# yakimenko_power_control.net
KiCad netlist of a schematic drawn in Altium Designer
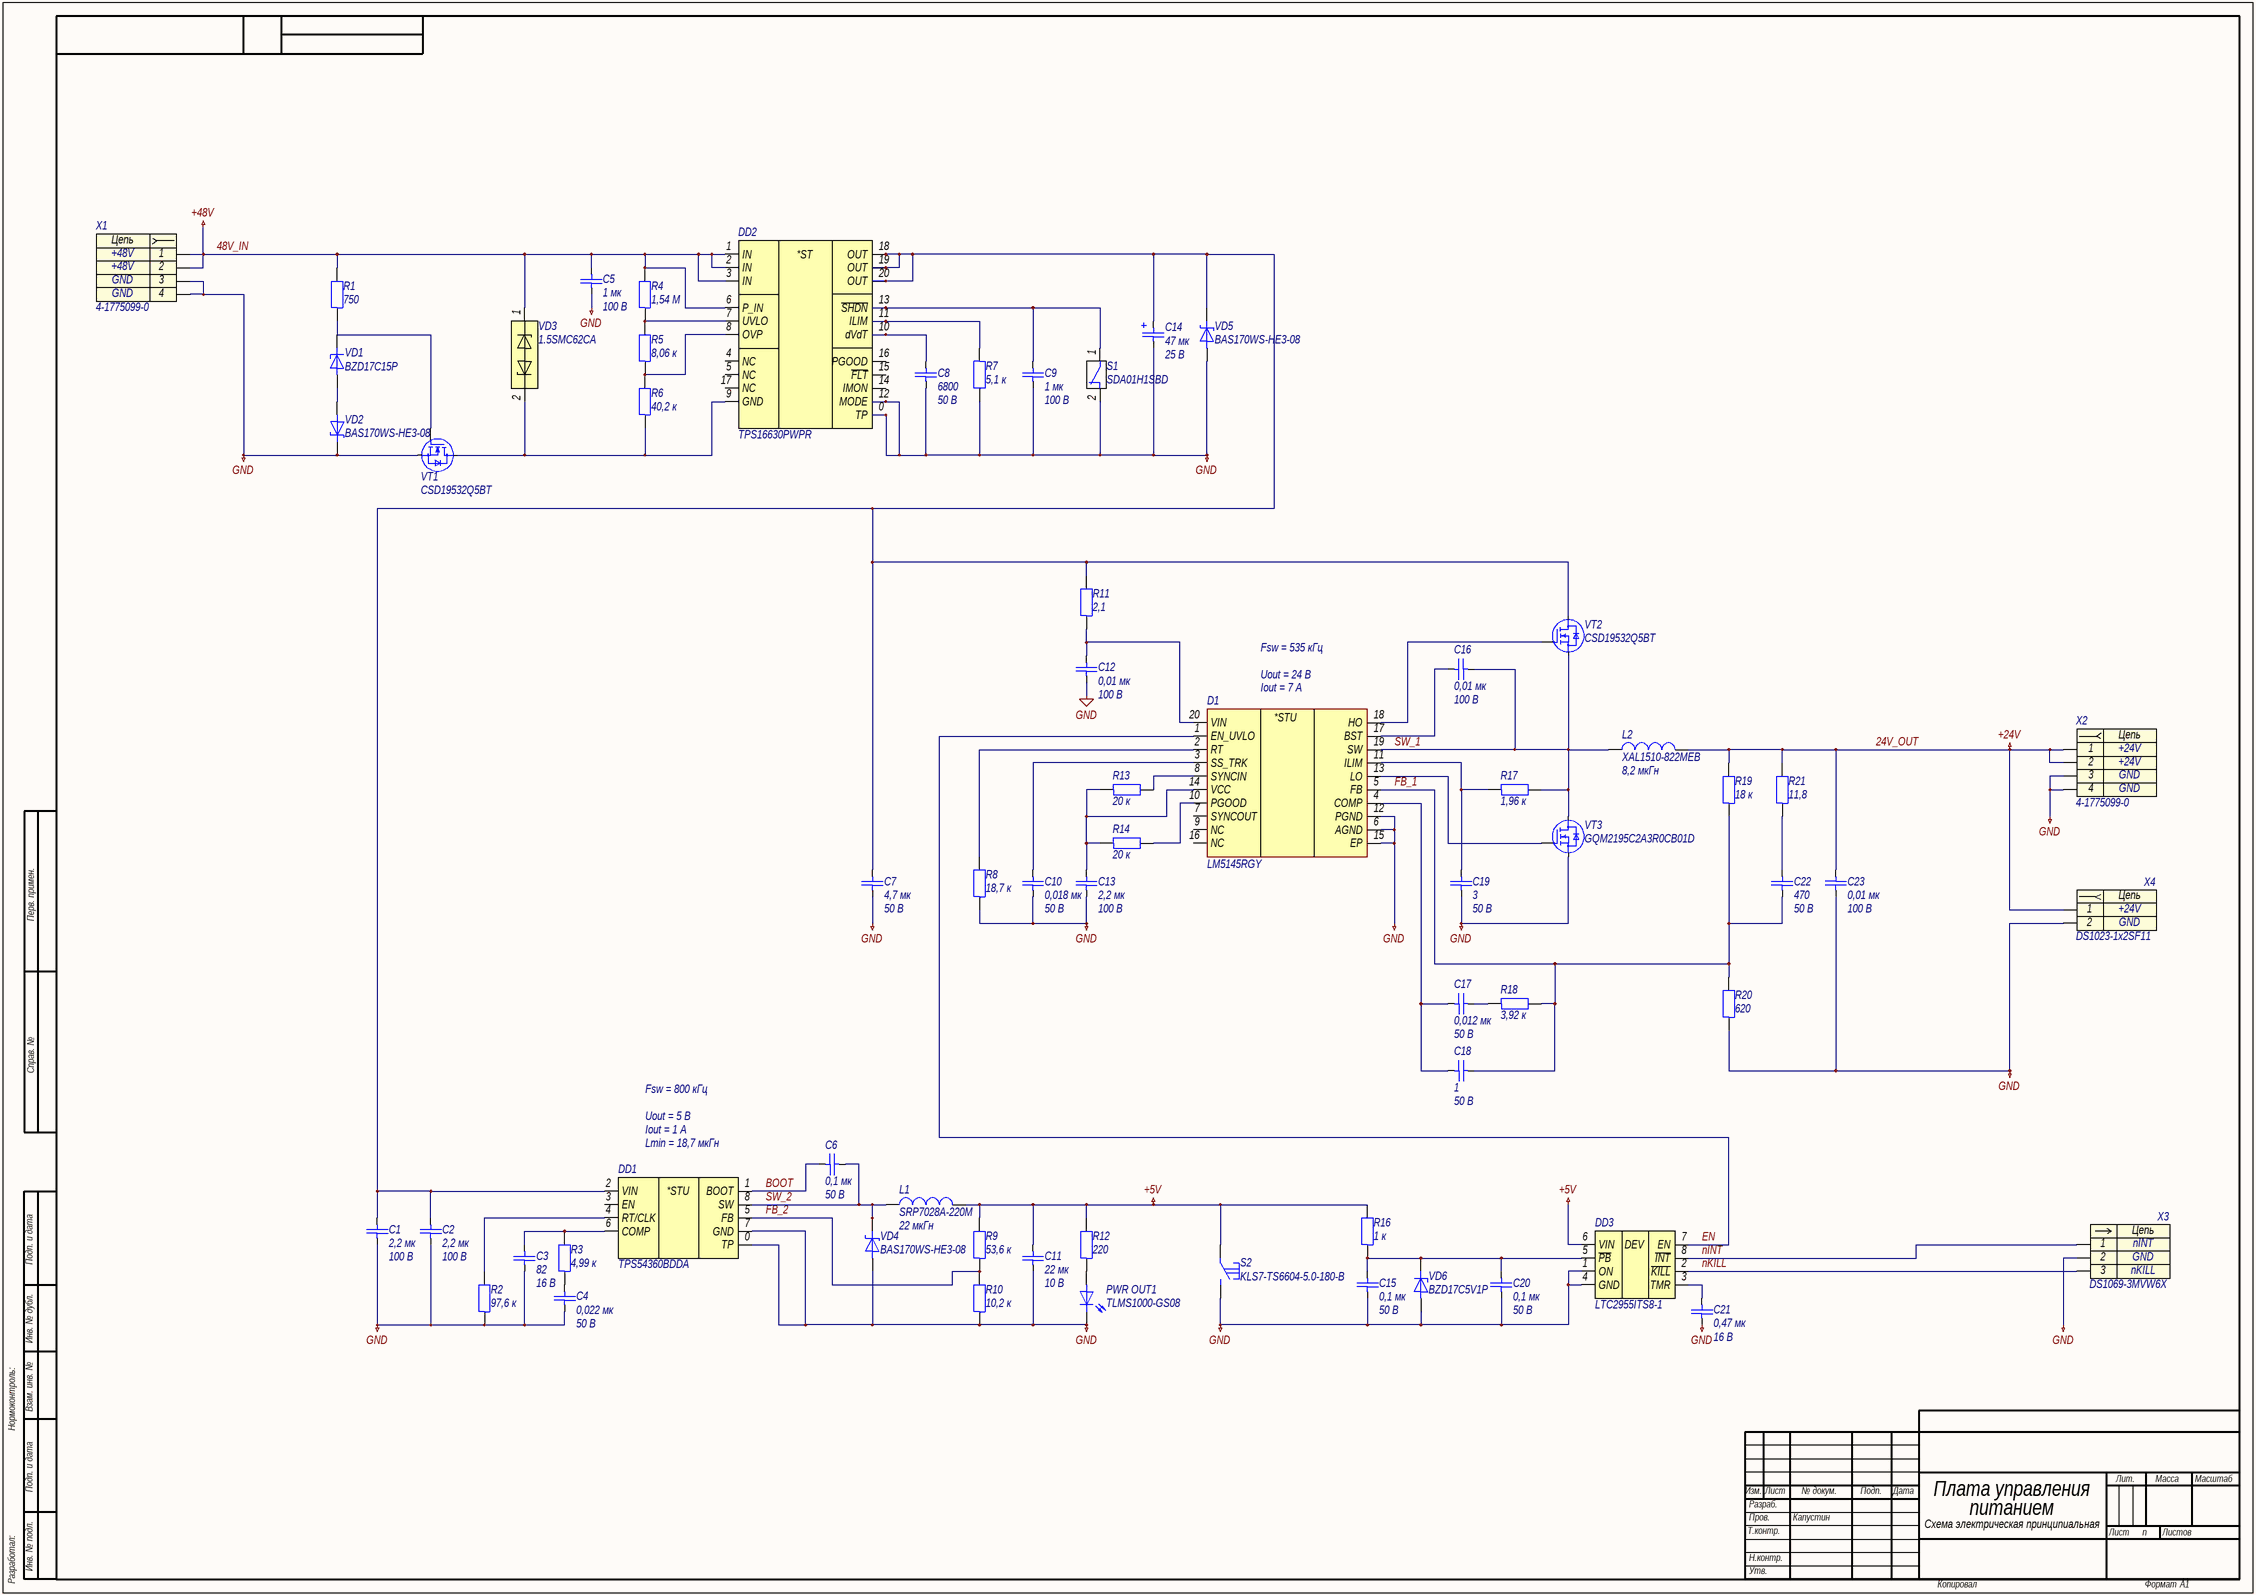
[diagram p0: yakimenko_power_control.SchDoc]

(export (version "E")
  (design (tool "Eeschema 10.0.6"))
  (components
    (comp (ref "C1")
      (value "2,2 мк")
      (footprint "C1206")
      (description "=Описание")
      (fields (field (name "НАПРЯЖЕНИЕ") "100 В"))
      (libsource (lib "Database_Students") (part "CAPACITOR-NONPOLAR"))
    )
    (comp (ref "C2")
      (value "2,2 мк")
      (footprint "C1206")
      (description "=Описание")
      (fields (field (name "НАПРЯЖЕНИЕ") "100 В"))
      (libsource (lib "Database_Students") (part "CAPACITOR-NONPOLAR"))
    )
    (comp (ref "C3")
      (value "82")
      (footprint "C0603")
      (description "=Описание")
      (fields (field (name "НАПРЯЖЕНИЕ") "16 В"))
      (libsource (lib "Database_Students") (part "CAPACITOR-NONPOLAR"))
    )
    (comp (ref "C4")
      (value "0,022 мк")
      (footprint "C0603")
      (description "=Описание")
      (fields (field (name "НАПРЯЖЕНИЕ") "50 В"))
      (libsource (lib "Database_Students") (part "CAPACITOR-NONPOLAR"))
    )
    (comp (ref "C5")
      (value "1 мк")
      (footprint "C1206")
      (description "=Описание")
      (fields (field (name "НАПРЯЖЕНИЕ") "100 В"))
      (libsource (lib "Database_Students") (part "CAPACITOR-NONPOLAR"))
    )
    (comp (ref "C6")
      (value "0,1 мк")
      (footprint "C0402")
      (description "=Описание")
      (fields (field (name "НАПРЯЖЕНИЕ") "50 В"))
      (libsource (lib "Database_Students") (part "CAPACITOR-NONPOLAR"))
    )
    (comp (ref "C7")
      (value "4,7 мк")
      (footprint "C0805")
      (description "=Описание")
      (fields (field (name "НАПРЯЖЕНИЕ") "50 В"))
      (libsource (lib "Database_Students") (part "CAPACITOR-NONPOLAR"))
    )
    (comp (ref "C8")
      (value "6800")
      (footprint "C0402")
      (description "=Описание")
      (fields (field (name "НАПРЯЖЕНИЕ") "50 В"))
      (libsource (lib "Database_Students") (part "CAPACITOR-NONPOLAR"))
    )
    (comp (ref "C9")
      (value "1 мк")
      (footprint "C1206")
      (description "=Описание")
      (fields (field (name "НАПРЯЖЕНИЕ") "100 В"))
      (libsource (lib "Database_Students") (part "CAPACITOR-NONPOLAR"))
    )
    (comp (ref "C10")
      (value "0,018 мк")
      (footprint "C0603")
      (description "=Описание")
      (fields (field (name "НАПРЯЖЕНИЕ") "50 В"))
      (libsource (lib "Database_Students") (part "CAPACITOR-NONPOLAR"))
    )
    (comp (ref "C11")
      (value "22 мк")
      (footprint "C0805")
      (description "=Описание")
      (fields (field (name "НАПРЯЖЕНИЕ") "10 В"))
      (libsource (lib "Database_Students") (part "CAPACITOR-NONPOLAR"))
    )
    (comp (ref "C12")
      (value "0,01 мк")
      (footprint "C0603")
      (description "=Описание")
      (fields (field (name "НАПРЯЖЕНИЕ") "100 В"))
      (libsource (lib "Database_Students") (part "CAPACITOR-NONPOLAR"))
    )
    (comp (ref "C13")
      (value "2,2 мк")
      (footprint "C1206")
      (description "=Описание")
      (fields (field (name "НАПРЯЖЕНИЕ") "100 В"))
      (libsource (lib "Database_Students") (part "CAPACITOR-NONPOLAR"))
    )
    (comp (ref "C14")
      (value "47 мк")
      (footprint "C7343-31")
      (description "=Описание")
      (fields (field (name "НАПРЯЖЕНИЕ") "25 В"))
      (libsource (lib "Database_Students") (part "CAPACITOR-POLAR"))
    )
    (comp (ref "C15")
      (value "0,1 мк")
      (footprint "C0402")
      (description "=Описание")
      (fields (field (name "НАПРЯЖЕНИЕ") "50 В"))
      (libsource (lib "Database_Students") (part "CAPACITOR-NONPOLAR"))
    )
    (comp (ref "C16")
      (value "0,01 мк")
      (footprint "C0603")
      (description "=Описание")
      (fields (field (name "НАПРЯЖЕНИЕ") "100 В"))
      (libsource (lib "Database_Students") (part "CAPACITOR-NONPOLAR"))
    )
    (comp (ref "C17")
      (value "0,012 мк")
      (footprint "C0603")
      (description "=Описание")
      (fields (field (name "НАПРЯЖЕНИЕ") "50 В"))
      (libsource (lib "Database_Students") (part "CAPACITOR-NONPOLAR"))
    )
    (comp (ref "C18")
      (value "1")
      (footprint "C0603")
      (description "=Описание")
      (fields (field (name "НАПРЯЖЕНИЕ") "50 В"))
      (libsource (lib "Database_Students") (part "CAPACITOR-NONPOLAR"))
    )
    (comp (ref "C19")
      (value "3")
      (footprint "C0603")
      (description "=Описание")
      (fields (field (name "НАПРЯЖЕНИЕ") "50 В"))
      (libsource (lib "Database_Students") (part "CAPACITOR-NONPOLAR"))
    )
    (comp (ref "C20")
      (value "0,1 мк")
      (footprint "C0402")
      (description "=Описание")
      (fields (field (name "НАПРЯЖЕНИЕ") "50 В"))
      (libsource (lib "Database_Students") (part "CAPACITOR-NONPOLAR"))
    )
    (comp (ref "C21")
      (value "0,47 мк")
      (footprint "C0603")
      (description "=Описание")
      (fields (field (name "НАПРЯЖЕНИЕ") "16 В"))
      (libsource (lib "Database_Students") (part "CAPACITOR-NONPOLAR"))
    )
    (comp (ref "C22")
      (value "470")
      (footprint "C0603")
      (description "=Описание")
      (fields (field (name "НАПРЯЖЕНИЕ") "50 В"))
      (libsource (lib "Database_Students") (part "CAPACITOR-NONPOLAR"))
    )
    (comp (ref "C23")
      (value "0,01 мк")
      (footprint "C0603")
      (description "=Описание")
      (fields (field (name "НАПРЯЖЕНИЕ") "100 В"))
      (libsource (lib "Database_Students") (part "CAPACITOR-NONPOLAR"))
    )
    (comp (ref "D1")
      (value "LM5145RGY")
      (footprint "VQFN-20-P50-450X350X100-L40X25-T270X170")
      (libsource (lib "yakimenko_power_control_lib") (part "LM5145RGY"))
    )
    (comp (ref "DD1")
      (value "TPS54360BDDA")
      (footprint "HSOIC-8-P127-490X390X170-L84X41-T310X240")
      (description "=Описание")
      (libsource (lib "Database_Students") (part "TPS54360BDDA"))
    )
    (comp (ref "DD2")
      (value "TPS16630PWPR")
      (footprint "HTSSOP-20-P65-650X440X120-L63X25-T296X296")
      (description "=Описание")
      (libsource (lib "Database_Students") (part "TPS16630PWPR"))
    )
    (comp (ref "DD3")
      (value "LTC2955ITS8-1")
      (footprint "SOT-23-8-P65-290X280X100")
      (description "=Описание")
      (libsource (lib "Database_Students") (part "LTC2955ITS8-1#TRMPBF"))
    )
    (comp (ref "L1")
      (value "SRP7028A-220M")
      (footprint "SRP-2-730X660X280")
      (description "=Описание")
      (fields (field (name "ИНДУКТИВНОСТЬ") "22 мкГн"))
      (libsource (lib "Database_Students") (part "INDUCTOR-COMMON"))
    )
    (comp (ref "L2")
      (value "XAL1510-822MEB")
      (footprint "XAL-2-1620X1520X1000")
      (description "=Описание")
      (fields (field (name "ИНДУКТИВНОСТЬ") "8,2 мкГн"))
      (libsource (lib "Database_Students") (part "INDUCTOR-COMMON"))
    )
    (comp (ref "PWR OUT1")
      (value "TLMS1000-GS08")
      (footprint "HL0603")
      (description "=Описание")
      (libsource (lib "Database_Students") (part "HL-COMMON"))
    )
    (comp (ref "R1")
      (value "750")
      (footprint "R0603")
      (description "=Описание")
      (libsource (lib "Database_Students") (part "R-COMMON"))
    )
    (comp (ref "R2")
      (value "97,6 к")
      (footprint "R0603")
      (description "=Описание")
      (libsource (lib "Database_Students") (part "R-COMMON"))
    )
    (comp (ref "R3")
      (value "4,99 к")
      (footprint "R0603")
      (description "=Описание")
      (libsource (lib "Database_Students") (part "R-COMMON"))
    )
    (comp (ref "R4")
      (value "1,54 М")
      (footprint "R0603")
      (description "=Описание")
      (libsource (lib "Database_Students") (part "R-COMMON"))
    )
    (comp (ref "R5")
      (value "8,06 к")
      (footprint "R0603")
      (description "=Описание")
      (libsource (lib "Database_Students") (part "R-COMMON"))
    )
    (comp (ref "R6")
      (value "40,2 к")
      (footprint "R0603")
      (description "=Описание")
      (libsource (lib "Database_Students") (part "R-COMMON"))
    )
    (comp (ref "R7")
      (value "5,1 к")
      (footprint "R0603")
      (description "=Описание")
      (libsource (lib "Database_Students") (part "R-COMMON"))
    )
    (comp (ref "R8")
      (value "18,7 к")
      (footprint "R0603")
      (description "=Описание")
      (libsource (lib "Database_Students") (part "RESISTOR-COMMON"))
    )
    (comp (ref "R9")
      (value "53,6 к")
      (footprint "R0603")
      (description "=Описание")
      (libsource (lib "Database_Students") (part "R-COMMON"))
    )
    (comp (ref "R10")
      (value "10,2 к")
      (footprint "R0603")
      (description "=Описание")
      (libsource (lib "Database_Students") (part "R-COMMON"))
    )
    (comp (ref "R11")
      (value "2,1")
      (footprint "R0603")
      (description "=Описание")
      (libsource (lib "Database_Students") (part "RESISTOR-COMMON"))
    )
    (comp (ref "R12")
      (value "220")
      (footprint "R0603")
      (description "=Описание")
      (libsource (lib "Database_Students") (part "R-COMMON"))
    )
    (comp (ref "R13")
      (value "20 к")
      (footprint "R0603")
      (description "=Описание")
      (libsource (lib "Database_Students") (part "RESISTOR-COMMON"))
    )
    (comp (ref "R14")
      (value "20 к")
      (footprint "R0603")
      (description "=Описание")
      (libsource (lib "Database_Students") (part "RESISTOR-COMMON"))
    )
    (comp (ref "R16")
      (value "1 к")
      (footprint "R0603")
      (description "=Описание")
      (libsource (lib "Database_Students") (part "RESISTOR-COMMON"))
    )
    (comp (ref "R17")
      (value "1,96 к")
      (footprint "R0603")
      (description "=Описание")
      (libsource (lib "Database_Students") (part "RESISTOR-COMMON"))
    )
    (comp (ref "R18")
      (value "3,92 к")
      (footprint "R0603")
      (description "=Описание")
      (libsource (lib "Database_Students") (part "RESISTOR-COMMON"))
    )
    (comp (ref "R19")
      (value "18 к")
      (footprint "R0603")
      (description "=Описание")
      (libsource (lib "Database_Students") (part "RESISTOR-COMMON"))
    )
    (comp (ref "R20")
      (value "620")
      (footprint "R0603")
      (description "=Описание")
      (libsource (lib "Database_Students") (part "RESISTOR-COMMON"))
    )
    (comp (ref "R21")
      (value "11,8")
      (footprint "R0603")
      (description "=Описание")
      (libsource (lib "Database_Students") (part "RESISTOR-COMMON"))
    )
    (comp (ref "S1")
      (value "SDA01H1SBD")
      (footprint "SDA01H1SBD")
      (description "=Описание")
      (libsource (lib "Database_Students") (part "SWITCH-2C"))
    )
    (comp (ref "S2")
      (value "KLS7-TS6604-5.0-180-B")
      (footprint "KLS7-TS6604-5.0-180-B")
      (description "=Описание")
      (libsource (lib "Database_Students") (part "BUTTON"))
    )
    (comp (ref "VD1")
      (value "BZD17C15P")
      (footprint "DO-219AB-280X180X108")
      (description "=Описание")
      (libsource (lib "Database_Students") (part "DIODE-ZENER"))
    )
    (comp (ref "VD2")
      (value "BAS170WS-HE3-08")
      (footprint "SOD-123-268X130X115")
      (description "=Описание")
      (libsource (lib "Database_Students") (part "DIODE-SCHOTTKY"))
    )
    (comp (ref "VD3")
      (value "1.5SMC62CA")
      (footprint "DO-214AB-790X590X262")
      (description "=Описание")
      (libsource (lib "Database_Students") (part "ZENER-BI-DIRECTIONAL"))
    )
    (comp (ref "VD4")
      (value "BAS170WS-HE3-08")
      (footprint "SOD-123-268X130X115")
      (description "=Описание")
      (libsource (lib "Database_Students") (part "DIODE-SCHOTTKY"))
    )
    (comp (ref "VD5")
      (value "BAS170WS-HE3-08")
      (footprint "SOD-123-268X130X115")
      (description "=Описание")
      (libsource (lib "Database_Students") (part "DIODE-SCHOTTKY"))
    )
    (comp (ref "VD6")
      (value "BZD17C5V1P")
      (footprint "DO-219AB-280X180X108")
      (description "=Описание")
      (libsource (lib "Database_Students") (part "DIODE-ZENER"))
    )
    (comp (ref "VT1")
      (value "CSD19532Q5BT")
      (footprint "VSONP-8-P127-600X500X105")
      (description "=Описание")
      (libsource (lib "Database_Students") (part "MOSFET-N-DIODE"))
    )
    (comp (ref "VT2")
      (value "CSD19532Q5BT")
      (footprint "VSONP-8-P127-600X500X105")
      (description "=Описание")
      (libsource (lib "Database_Students") (part "MOSFET-N-DIODE"))
    )
    (comp (ref "VT3")
      (value "GQM2195C2A3R0CB01D")
      (footprint "VSONP-8-P127-600X500X105")
      (description "=Описание")
      (libsource (lib "Database_Students") (part "MOSFET-N-DIODE"))
    )
    (comp (ref "X1")
      (value "4-1775099-0")
      (footprint "4-1775099-0")
      (description "=Описание")
      (libsource (lib "") (part "HEADER-4-SCT_1"))
    )
    (comp (ref "X2")
      (value "4-1775099-0")
      (footprint "4-1775099-0")
      (description "=Описание")
      (libsource (lib "Database_Students") (part "HEADER-4-SCT"))
    )
    (comp (ref "X3")
      (value "DS1069-3MVW6X")
      (footprint "DS1069-3MVW6X")
      (description "=Описание")
      (libsource (lib "Database_Students") (part "HEADER-3-PLG"))
    )
    (comp (ref "X4")
      (value "DS1023-1x2SF11")
      (footprint "DS1023-1X2SF11")
      (description "=Описание")
      (libsource (lib "Database_Students") (part "HEADER-2-SCT"))
    )
  )
  (nets
    (net (code "1") (name "+5V") (class "Default")
      (node (ref "C11") (pin "1") (pinfunction "1_1") (pintype "passive"))
      (node (ref "DD3") (pin "6") (pinfunction "VIN_6") (pintype "passive"))
      (node (ref "L1") (pin "2") (pinfunction "2_2") (pintype "passive"))
      (node (ref "R12") (pin "2") (pinfunction "2_2") (pintype "passive"))
      (node (ref "R16") (pin "2") (pinfunction "2_2") (pintype "passive"))
      (node (ref "R9") (pin "2") (pinfunction "2_2") (pintype "passive"))
      (node (ref "S2") (pin "1") (pinfunction "1_1") (pintype "passive"))
    )
    (net (code "2") (name "+24V") (class "Default")
      (node (ref "C23") (pin "2") (pinfunction "2_2") (pintype "passive"))
      (node (ref "L2") (pin "2") (pinfunction "2_2") (pintype "passive"))
      (node (ref "R19") (pin "2") (pinfunction "2_2") (pintype "passive"))
      (node (ref "R21") (pin "2") (pinfunction "2_2") (pintype "passive"))
      (node (ref "X2") (pin "1") (pinfunction "1_1") (pintype "passive"))
      (node (ref "X2") (pin "2") (pinfunction "2_2") (pintype "passive"))
      (node (ref "X4") (pin "1") (pinfunction "1_1") (pintype "passive"))
    )
    (net (code "3") (name "+48V") (class "Default")
      (node (ref "C5") (pin "1") (pinfunction "1_1") (pintype "passive"))
      (node (ref "DD2") (pin "1") (pinfunction "IN_1") (pintype "passive"))
      (node (ref "DD2") (pin "2") (pinfunction "IN_2") (pintype "passive"))
      (node (ref "DD2") (pin "3") (pinfunction "IN_3") (pintype "passive"))
      (node (ref "DD2") (pin "6") (pinfunction "P_IN_6") (pintype "passive"))
      (node (ref "R1") (pin "2") (pinfunction "2_2") (pintype "passive"))
      (node (ref "R4") (pin "2") (pinfunction "2_2") (pintype "passive"))
      (node (ref "VD3") (pin "1") (pinfunction "1_1") (pintype "passive"))
      (node (ref "X1") (pin "1") (pinfunction "1_1") (pintype "passive"))
      (node (ref "X1") (pin "2") (pinfunction "2_2") (pintype "passive"))
    )
    (net (code "4") (name "/BOOT") (class "Default")
      (node (ref "C6") (pin "2") (pinfunction "2_2") (pintype "passive"))
      (node (ref "DD1") (pin "1") (pinfunction "BOOT_1") (pintype "passive"))
    )
    (net (code "5") (name "/EN") (class "Default")
      (node (ref "D1") (pin "1") (pinfunction "EN_UVLO_1") (pintype "passive"))
      (node (ref "DD3") (pin "7") (pinfunction "EN_7") (pintype "passive"))
    )
    (net (code "6") (name "/FB_1") (class "Default")
      (node (ref "C18") (pin "1") (pinfunction "1_1") (pintype "passive"))
      (node (ref "C22") (pin "2") (pinfunction "2_2") (pintype "passive"))
      (node (ref "D1") (pin "5") (pinfunction "FB_5") (pintype "passive"))
      (node (ref "R18") (pin "2") (pinfunction "2_2") (pintype "passive"))
      (node (ref "R19") (pin "1") (pinfunction "1_1") (pintype "passive"))
      (node (ref "R20") (pin "2") (pinfunction "2_2") (pintype "passive"))
    )
    (net (code "7") (name "/FB_2") (class "Default")
      (node (ref "DD1") (pin "5") (pinfunction "FB_5") (pintype "passive"))
      (node (ref "R10") (pin "2") (pinfunction "2_2") (pintype "passive"))
      (node (ref "R9") (pin "1") (pinfunction "1_1") (pintype "passive"))
    )
    (net (code "8") (name "/SW_1") (class "Default")
      (node (ref "C16") (pin "2") (pinfunction "2_2") (pintype "passive"))
      (node (ref "D1") (pin "19") (pinfunction "SW_19") (pintype "passive"))
      (node (ref "L2") (pin "1") (pinfunction "1_1") (pintype "passive"))
      (node (ref "R17") (pin "2") (pinfunction "2_2") (pintype "passive"))
      (node (ref "VT2") (pin "S") (pinfunction "S_S") (pintype "passive"))
      (node (ref "VT3") (pin "D") (pinfunction "D_D") (pintype "passive"))
    )
    (net (code "9") (name "/SW_2") (class "Default")
      (node (ref "C6") (pin "1") (pinfunction "1_1") (pintype "passive"))
      (node (ref "DD1") (pin "8") (pinfunction "SW_8") (pintype "passive"))
      (node (ref "L1") (pin "1") (pinfunction "1_1") (pintype "passive"))
      (node (ref "VD4") (pin "1") (pinfunction "1_1") (pintype "passive"))
    )
    (net (code "10") (name "/nINT") (class "Default")
      (node (ref "DD3") (pin "8") (pinfunction "~{INT}_8") (pintype "passive"))
      (node (ref "X3") (pin "1") (pinfunction "1_1") (pintype "passive"))
    )
    (net (code "11") (name "/nKILL") (class "Default")
      (node (ref "DD3") (pin "2") (pinfunction "~{KILL}_2") (pintype "passive"))
      (node (ref "X3") (pin "3") (pinfunction "3_3") (pintype "passive"))
    )
    (net (code "12") (name "GND") (class "Default")
      (node (ref "C1") (pin "2") (pinfunction "2_2") (pintype "passive"))
      (node (ref "C10") (pin "2") (pinfunction "2_2") (pintype "passive"))
      (node (ref "C11") (pin "2") (pinfunction "2_2") (pintype "passive"))
      (node (ref "C12") (pin "2") (pinfunction "2_2") (pintype "passive"))
      (node (ref "C13") (pin "2") (pinfunction "2_2") (pintype "passive"))
      (node (ref "C14") (pin "2") (pinfunction "2_2") (pintype "passive"))
      (node (ref "C15") (pin "2") (pinfunction "2_2") (pintype "passive"))
      (node (ref "C19") (pin "2") (pinfunction "2_2") (pintype "passive"))
      (node (ref "C2") (pin "2") (pinfunction "2_2") (pintype "passive"))
      (node (ref "C20") (pin "2") (pinfunction "2_2") (pintype "passive"))
      (node (ref "C21") (pin "2") (pinfunction "2_2") (pintype "passive"))
      (node (ref "C23") (pin "1") (pinfunction "1_1") (pintype "passive"))
      (node (ref "C3") (pin "2") (pinfunction "2_2") (pintype "passive"))
      (node (ref "C4") (pin "2") (pinfunction "2_2") (pintype "passive"))
      (node (ref "C5") (pin "2") (pinfunction "2_2") (pintype "passive"))
      (node (ref "C7") (pin "2") (pinfunction "2_2") (pintype "passive"))
      (node (ref "C8") (pin "2") (pinfunction "2_2") (pintype "passive"))
      (node (ref "C9") (pin "2") (pinfunction "2_2") (pintype "passive"))
      (node (ref "D1") (pin "12") (pinfunction "PGND_12") (pintype "passive"))
      (node (ref "D1") (pin "15") (pinfunction "EP_15") (pintype "passive"))
      (node (ref "D1") (pin "6") (pinfunction "AGND_6") (pintype "passive"))
      (node (ref "DD1") (pin "0") (pinfunction "TP_0") (pintype "passive"))
      (node (ref "DD1") (pin "7") (pinfunction "GND_7") (pintype "passive"))
      (node (ref "DD2") (pin "0") (pinfunction "TP_0") (pintype "passive"))
      (node (ref "DD2") (pin "12") (pinfunction "MODE_12") (pintype "passive"))
      (node (ref "DD3") (pin "1") (pinfunction "ON_1") (pintype "passive"))
      (node (ref "DD3") (pin "4") (pinfunction "GND_4") (pintype "passive"))
      (node (ref "PWR OUT1") (pin "1") (pinfunction "1_1") (pintype "passive"))
      (node (ref "R10") (pin "1") (pinfunction "1_1") (pintype "passive"))
      (node (ref "R2") (pin "1") (pinfunction "1_1") (pintype "passive"))
      (node (ref "R20") (pin "1") (pinfunction "1_1") (pintype "passive"))
      (node (ref "R7") (pin "2") (pinfunction "2_2") (pintype "passive"))
      (node (ref "R8") (pin "1") (pinfunction "1_1") (pintype "passive"))
      (node (ref "S1") (pin "2") (pinfunction "2_2") (pintype "passive"))
      (node (ref "S2") (pin "2") (pinfunction "2_2") (pintype "passive"))
      (node (ref "VD2") (pin "1") (pinfunction "1_1") (pintype "passive"))
      (node (ref "VD4") (pin "2") (pinfunction "2_2") (pintype "passive"))
      (node (ref "VD5") (pin "2") (pinfunction "2_2") (pintype "passive"))
      (node (ref "VD6") (pin "2") (pinfunction "2_2") (pintype "passive"))
      (node (ref "VT1") (pin "S") (pinfunction "S_S") (pintype "passive"))
      (node (ref "VT3") (pin "S") (pinfunction "S_S") (pintype "passive"))
      (node (ref "X1") (pin "3") (pinfunction "3_3") (pintype "passive"))
      (node (ref "X1") (pin "4") (pinfunction "4_4") (pintype "passive"))
      (node (ref "X2") (pin "3") (pinfunction "3_3") (pintype "passive"))
      (node (ref "X2") (pin "4") (pinfunction "4_4") (pintype "passive"))
      (node (ref "X3") (pin "2") (pinfunction "2_2") (pintype "passive"))
      (node (ref "X4") (pin "2") (pinfunction "2_2") (pintype "passive"))
    )
    (net (code "13") (name "Net-(C4-Pad1)") (class "Default")
      (node (ref "C4") (pin "1") (pinfunction "1_1") (pintype "passive"))
      (node (ref "R3") (pin "1") (pinfunction "1_1") (pintype "passive"))
    )
    (net (code "14") (name "Net-(C17-Pad1)") (class "Default")
      (node (ref "C17") (pin "1") (pinfunction "1_1") (pintype "passive"))
      (node (ref "R18") (pin "1") (pinfunction "1_1") (pintype "passive"))
    )
    (net (code "15") (name "Net-(C22-Pad1)") (class "Default")
      (node (ref "C22") (pin "1") (pinfunction "1_1") (pintype "passive"))
      (node (ref "R21") (pin "1") (pinfunction "1_1") (pintype "passive"))
    )
    (net (code "16") (name "Net-(D1-BST)") (class "Default")
      (node (ref "C16") (pin "1") (pinfunction "1_1") (pintype "passive"))
      (node (ref "D1") (pin "17") (pinfunction "BST_17") (pintype "passive"))
    )
    (net (code "17") (name "Net-(D1-COMP)") (class "Default")
      (node (ref "C17") (pin "2") (pinfunction "2_2") (pintype "passive"))
      (node (ref "C18") (pin "2") (pinfunction "2_2") (pintype "passive"))
      (node (ref "D1") (pin "4") (pinfunction "COMP_4") (pintype "passive"))
    )
    (net (code "18") (name "Net-(D1-HO)") (class "Default")
      (node (ref "D1") (pin "18") (pinfunction "HO_18") (pintype "passive"))
      (node (ref "VT2") (pin "G") (pinfunction "G_G") (pintype "passive"))
    )
    (net (code "19") (name "Net-(D1-ILIM)") (class "Default")
      (node (ref "C19") (pin "1") (pinfunction "1_1") (pintype "passive"))
      (node (ref "D1") (pin "11") (pinfunction "ILIM_11") (pintype "passive"))
      (node (ref "R17") (pin "1") (pinfunction "1_1") (pintype "passive"))
    )
    (net (code "20") (name "Net-(D1-LO)") (class "Default")
      (node (ref "D1") (pin "13") (pinfunction "LO_13") (pintype "passive"))
      (node (ref "VT3") (pin "G") (pinfunction "G_G") (pintype "passive"))
    )
    (net (code "21") (name "Net-(D1-PGOOD)") (class "Default")
      (node (ref "D1") (pin "10") (pinfunction "PGOOD_10") (pintype "passive"))
      (node (ref "R14") (pin "2") (pinfunction "2_2") (pintype "passive"))
    )
    (net (code "22") (name "Net-(D1-RT)") (class "Default")
      (node (ref "D1") (pin "2") (pinfunction "RT_2") (pintype "passive"))
      (node (ref "R8") (pin "2") (pinfunction "2_2") (pintype "passive"))
    )
    (net (code "23") (name "Net-(D1-SS_TRK)") (class "Default")
      (node (ref "C10") (pin "1") (pinfunction "1_1") (pintype "passive"))
      (node (ref "D1") (pin "3") (pinfunction "SS_TRK_3") (pintype "passive"))
    )
    (net (code "24") (name "Net-(D1-SYNCIN)") (class "Default")
      (node (ref "D1") (pin "8") (pinfunction "SYNCIN_8") (pintype "passive"))
      (node (ref "R13") (pin "2") (pinfunction "2_2") (pintype "passive"))
    )
    (net (code "25") (name "Net-(D1-VCC)") (class "Default")
      (node (ref "C13") (pin "1") (pinfunction "1_1") (pintype "passive"))
      (node (ref "D1") (pin "14") (pinfunction "VCC_14") (pintype "passive"))
      (node (ref "R13") (pin "1") (pinfunction "1_1") (pintype "passive"))
      (node (ref "R14") (pin "1") (pinfunction "1_1") (pintype "passive"))
    )
    (net (code "26") (name "Net-(D1-VIN)") (class "Default")
      (node (ref "C12") (pin "1") (pinfunction "1_1") (pintype "passive"))
      (node (ref "D1") (pin "20") (pinfunction "VIN_20") (pintype "passive"))
      (node (ref "R11") (pin "1") (pinfunction "1_1") (pintype "passive"))
    )
    (net (code "27") (name "Net-(DD1-COMP)") (class "Default")
      (node (ref "C3") (pin "1") (pinfunction "1_1") (pintype "passive"))
      (node (ref "DD1") (pin "6") (pinfunction "COMP_6") (pintype "passive"))
      (node (ref "R3") (pin "2") (pinfunction "2_2") (pintype "passive"))
    )
    (net (code "28") (name "Net-(DD1-RT{slash}CLK)") (class "Default")
      (node (ref "DD1") (pin "4") (pinfunction "RT/CLK_4") (pintype "passive"))
      (node (ref "R2") (pin "2") (pinfunction "2_2") (pintype "passive"))
    )
    (net (code "29") (name "Net-(DD1-VIN)") (class "Default")
      (node (ref "C1") (pin "1") (pinfunction "1_1") (pintype "passive"))
      (node (ref "C14") (pin "1") (pinfunction "1_1") (pintype "passive"))
      (node (ref "C2") (pin "1") (pinfunction "1_1") (pintype "passive"))
      (node (ref "C7") (pin "1") (pinfunction "1_1") (pintype "passive"))
      (node (ref "DD1") (pin "2") (pinfunction "VIN_2") (pintype "passive"))
      (node (ref "DD2") (pin "18") (pinfunction "OUT_18") (pintype "passive"))
      (node (ref "DD2") (pin "19") (pinfunction "OUT_19") (pintype "passive"))
      (node (ref "DD2") (pin "20") (pinfunction "OUT_20") (pintype "passive"))
      (node (ref "R11") (pin "2") (pinfunction "2_2") (pintype "passive"))
      (node (ref "VD5") (pin "1") (pinfunction "1_1") (pintype "passive"))
      (node (ref "VT2") (pin "D") (pinfunction "D_D") (pintype "passive"))
    )
    (net (code "30") (name "Net-(DD2-GND)") (class "Default")
      (node (ref "DD2") (pin "9") (pinfunction "GND_9") (pintype "passive"))
      (node (ref "R6") (pin "1") (pinfunction "1_1") (pintype "passive"))
      (node (ref "VD3") (pin "2") (pinfunction "2_2") (pintype "passive"))
      (node (ref "VT1") (pin "D") (pinfunction "D_D") (pintype "passive"))
    )
    (net (code "31") (name "Net-(DD2-ILIM)") (class "Default")
      (node (ref "DD2") (pin "11") (pinfunction "ILIM_11") (pintype "passive"))
      (node (ref "R7") (pin "1") (pinfunction "1_1") (pintype "passive"))
    )
    (net (code "32") (name "Net-(DD2-OVP)") (class "Default")
      (node (ref "DD2") (pin "8") (pinfunction "OVP_8") (pintype "passive"))
      (node (ref "R5") (pin "1") (pinfunction "1_1") (pintype "passive"))
      (node (ref "R6") (pin "2") (pinfunction "2_2") (pintype "passive"))
    )
    (net (code "33") (name "Net-(DD2-UVLO)") (class "Default")
      (node (ref "DD2") (pin "7") (pinfunction "UVLO_7") (pintype "passive"))
      (node (ref "R4") (pin "1") (pinfunction "1_1") (pintype "passive"))
      (node (ref "R5") (pin "2") (pinfunction "2_2") (pintype "passive"))
    )
    (net (code "34") (name "Net-(DD2-dVdT)") (class "Default")
      (node (ref "C8") (pin "1") (pinfunction "1_1") (pintype "passive"))
      (node (ref "DD2") (pin "10") (pinfunction "dVdT_10") (pintype "passive"))
    )
    (net (code "35") (name "Net-(DD2-~{SHDN})") (class "Default")
      (node (ref "C9") (pin "1") (pinfunction "1_1") (pintype "passive"))
      (node (ref "DD2") (pin "13") (pinfunction "~{SHDN}_13") (pintype "passive"))
      (node (ref "S1") (pin "1") (pinfunction "1_1") (pintype "passive"))
    )
    (net (code "36") (name "Net-(DD3-TMR)") (class "Default")
      (node (ref "C21") (pin "1") (pinfunction "1_1") (pintype "passive"))
      (node (ref "DD3") (pin "3") (pinfunction "TMR_3") (pintype "passive"))
    )
    (net (code "37") (name "Net-(DD3-~{PB})") (class "Default")
      (node (ref "C15") (pin "1") (pinfunction "1_1") (pintype "passive"))
      (node (ref "C20") (pin "1") (pinfunction "1_1") (pintype "passive"))
      (node (ref "DD3") (pin "5") (pinfunction "~{PB}_5") (pintype "passive"))
      (node (ref "R16") (pin "1") (pinfunction "1_1") (pintype "passive"))
      (node (ref "VD6") (pin "1") (pinfunction "1_1") (pintype "passive"))
    )
    (net (code "38") (name "Net-(PWR OUT1-Pad2)") (class "Default")
      (node (ref "PWR OUT1") (pin "2") (pinfunction "2_2") (pintype "passive"))
      (node (ref "R12") (pin "1") (pinfunction "1_1") (pintype "passive"))
    )
    (net (code "39") (name "Net-(R1-Pad1)") (class "Default")
      (node (ref "R1") (pin "1") (pinfunction "1_1") (pintype "passive"))
      (node (ref "VD1") (pin "1") (pinfunction "1_1") (pintype "passive"))
      (node (ref "VT1") (pin "G") (pinfunction "G_G") (pintype "passive"))
    )
    (net (code "40") (name "Net-(VD1-Pad2)") (class "Default")
      (node (ref "VD1") (pin "2") (pinfunction "2_2") (pintype "passive"))
      (node (ref "VD2") (pin "2") (pinfunction "2_2") (pintype "passive"))
    )
    (net (code "41") (name "unconnected-(D1-NC-Pad9)") (class "Default")
      (node (ref "D1") (pin "9") (pinfunction "NC_9") (pintype "passive"))
    )
    (net (code "42") (name "unconnected-(D1-NC-Pad16)") (class "Default")
      (node (ref "D1") (pin "16") (pinfunction "NC_16") (pintype "passive"))
    )
    (net (code "43") (name "unconnected-(D1-SYNCOUT-Pad7)") (class "Default")
      (node (ref "D1") (pin "7") (pinfunction "SYNCOUT_7") (pintype "passive"))
    )
    (net (code "44") (name "unconnected-(DD1-EN-Pad3)") (class "Default")
      (node (ref "DD1") (pin "3") (pinfunction "EN_3") (pintype "passive"))
    )
    (net (code "45") (name "unconnected-(DD2-IMON-Pad14)") (class "Default")
      (node (ref "DD2") (pin "14") (pinfunction "IMON_14") (pintype "passive"))
    )
    (net (code "46") (name "unconnected-(DD2-NC-Pad4)") (class "Default")
      (node (ref "DD2") (pin "4") (pinfunction "NC_4") (pintype "passive"))
    )
    (net (code "47") (name "unconnected-(DD2-NC-Pad5)") (class "Default")
      (node (ref "DD2") (pin "5") (pinfunction "NC_5") (pintype "passive"))
    )
    (net (code "48") (name "unconnected-(DD2-NC-Pad17)") (class "Default")
      (node (ref "DD2") (pin "17") (pinfunction "NC_17") (pintype "passive"))
    )
    (net (code "49") (name "unconnected-(DD2-PGOOD-Pad16)") (class "Default")
      (node (ref "DD2") (pin "16") (pinfunction "PGOOD_16") (pintype "passive"))
    )
    (net (code "50") (name "unconnected-(DD2-~{FLT}-Pad15)") (class "Default")
      (node (ref "DD2") (pin "15") (pinfunction "~{FLT}_15") (pintype "passive"))
    )
  )
)
